# Sheet1.net
KiCad netlist of a schematic drawn in Altium Designer
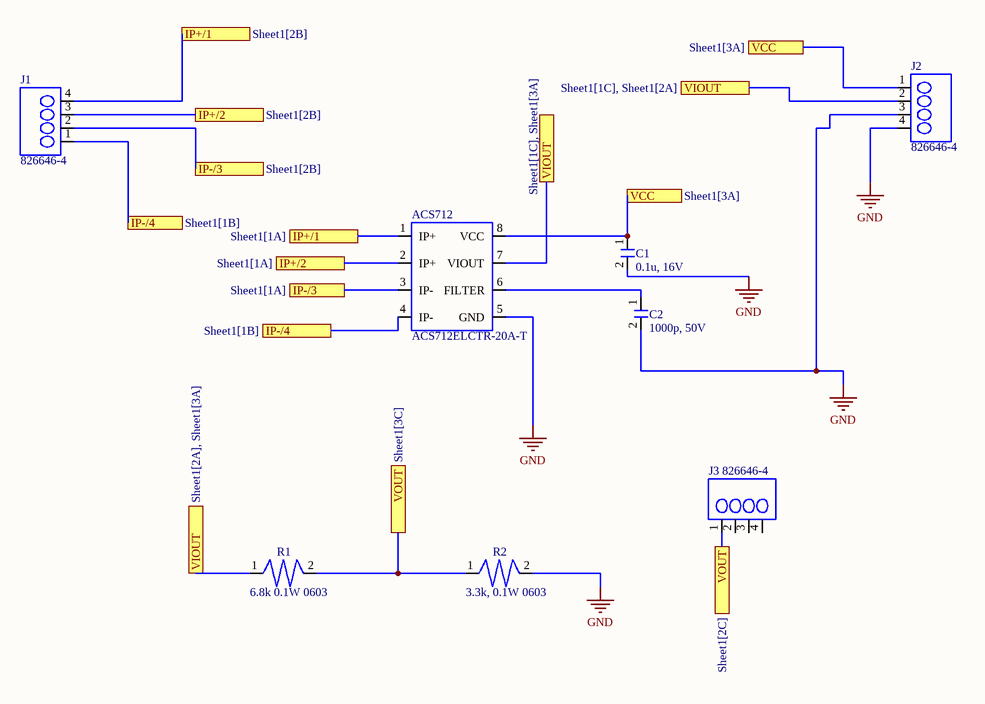
[diagram p0: Sheet1.SchDoc]

(export (version "E")
  (design (tool "Eeschema 10.0.6"))
  (components
    (comp (ref "ACS712")
      (value "ACS712ELCTR-20A-T")
      (footprint "8SOIC")
      (description "Analog Circuit, 1 Func, BICMOS, PDSO8")
      (fields (field (name "MANUFACTURER") "Allegro MicroSystems"))
      (libsource (lib "Schlib1") (part "ACS712ELCTR-20A-T"))
    )
    (comp (ref "C1")
      (value "0.1u, 16V")
      (footprint "0603 Capacitor")
      (fields
        (field (name "MANUFACTURER") "Yageo")
        (field (name "MANUFACTURER PART NUMBER") "CC0603KRX7R7BB104")
      )
      (libsource (lib "Schlib1") (part "CC0603KRX7R7BB104"))
    )
    (comp (ref "C2")
      (value "1000p, 50V")
      (footprint "0603 Capacitor")
      (fields
        (field (name "MANUFACTURER") "Yageo")
        (field (name "MANUFACTURER PART NUMBER") "CC0603KRX7R9BB102")
      )
      (libsource (lib "Schlib1") (part "CC0603KRX7R9BB102"))
    )
    (comp (ref "J1")
      (value "826646-4")
      (footprint "Header-4Pin")
      (description "Board Connector, 4 Contact(s), 1 Row(s), Male, Straight, Solder Terminal, Green Insulator")
      (fields (field (name "MANUFACTURER") "TE Connectivity"))
      (libsource (lib "") (part "826646-4_1"))
    )
    (comp (ref "J2")
      (value "826646-4")
      (footprint "Header-4Pin")
      (description "Board Connector, 4 Contact(s), 1 Row(s), Male, Straight, Solder Terminal, Green Insulator")
      (fields (field (name "MANUFACTURER") "TE Connectivity"))
      (libsource (lib "") (part "826646-4_2"))
    )
    (comp (ref "J3")
      (value "826646-4")
      (footprint "Header-4Pin")
      (description "Board Connector, 4 Contact(s), 1 Row(s), Male, Straight, Solder Terminal, Green Insulator")
      (fields (field (name "MANUFACTURER") "TE Connectivity"))
      (libsource (lib "Schlib1") (part "826646-4"))
    )
    (comp (ref "R1")
      (value "6.8k 0.1W 0603")
      (footprint "0603 Resisitor")
      (fields
        (field (name "MANUFACTURER") "Yageo")
        (field (name "MANUFACTURER PART NUMBER") "RC0603FR-106K8L")
        (field (name "TOLERANCE") "1%")
      )
      (libsource (lib "Schlib1") (part "RC0603FR-106K8L"))
    )
    (comp (ref "R2")
      (value "3.3k, 0.1W 0603")
      (footprint "0603 Resisitor")
      (fields
        (field (name "MANUFACTURER") "Yageo")
        (field (name "MANUFACTURER PART NUMBER") "RC0603FR-073K3L")
        (field (name "TOLERANCE") "1%")
      )
      (libsource (lib "Schlib1") (part "RC0603FR-073K3L"))
    )
  )
  (nets
    (net (code "1") (name "/IP+{slash}1") (class "Default")
      (node (ref "ACS712") (pin "1") (pinfunction "IP+_1") (pintype "passive"))
      (node (ref "J1") (pin "4") (pintype "passive"))
    )
    (net (code "2") (name "/IP+{slash}2") (class "Default")
      (node (ref "ACS712") (pin "2") (pinfunction "IP+_2") (pintype "passive"))
      (node (ref "J1") (pin "3") (pintype "passive"))
    )
    (net (code "3") (name "/IP-{slash}3") (class "Default")
      (node (ref "ACS712") (pin "3") (pinfunction "IP-_3") (pintype "passive"))
      (node (ref "J1") (pin "2") (pintype "passive"))
    )
    (net (code "4") (name "/IP-{slash}4") (class "Default")
      (node (ref "ACS712") (pin "4") (pinfunction "IP-_4") (pintype "passive"))
      (node (ref "J1") (pin "1") (pintype "passive"))
    )
    (net (code "5") (name "/VCC") (class "Default")
      (node (ref "ACS712") (pin "8") (pinfunction "VCC_8") (pintype "passive"))
      (node (ref "C1") (pin "1") (pintype "passive"))
      (node (ref "J2") (pin "1") (pintype "passive"))
    )
    (net (code "6") (name "/VIOUT") (class "Default")
      (node (ref "ACS712") (pin "7") (pinfunction "VIOUT_7") (pintype "passive"))
      (node (ref "J2") (pin "2") (pintype "passive"))
      (node (ref "R1") (pin "1") (pinfunction "0_1") (pintype "passive"))
    )
    (net (code "7") (name "/VOUT") (class "Default")
      (node (ref "J3") (pin "1") (pintype "passive"))
      (node (ref "R1") (pin "2") (pinfunction "1_2") (pintype "passive"))
      (node (ref "R2") (pin "1") (pinfunction "0_1") (pintype "passive"))
    )
    (net (code "8") (name "GND") (class "Default")
      (node (ref "ACS712") (pin "5") (pinfunction "GND_5") (pintype "passive"))
      (node (ref "C1") (pin "2") (pintype "passive"))
      (node (ref "C2") (pin "2") (pintype "passive"))
      (node (ref "J2") (pin "3") (pintype "passive"))
      (node (ref "J2") (pin "4") (pintype "passive"))
      (node (ref "R2") (pin "2") (pinfunction "1_2") (pintype "passive"))
    )
    (net (code "9") (name "Net-(ACS712-FILTER)") (class "Default")
      (node (ref "ACS712") (pin "6") (pinfunction "FILTER_6") (pintype "passive"))
      (node (ref "C2") (pin "1") (pintype "passive"))
    )
    (net (code "10") (name "unconnected-(J3-Pad2)") (class "Default")
      (node (ref "J3") (pin "2") (pintype "passive"))
    )
    (net (code "11") (name "unconnected-(J3-Pad3)") (class "Default")
      (node (ref "J3") (pin "3") (pintype "passive"))
    )
    (net (code "12") (name "unconnected-(J3-Pad4)") (class "Default")
      (node (ref "J3") (pin "4") (pintype "passive"))
    )
  )
)
